# ScreenBoard.net
KiCad netlist of a schematic drawn in Altium Designer
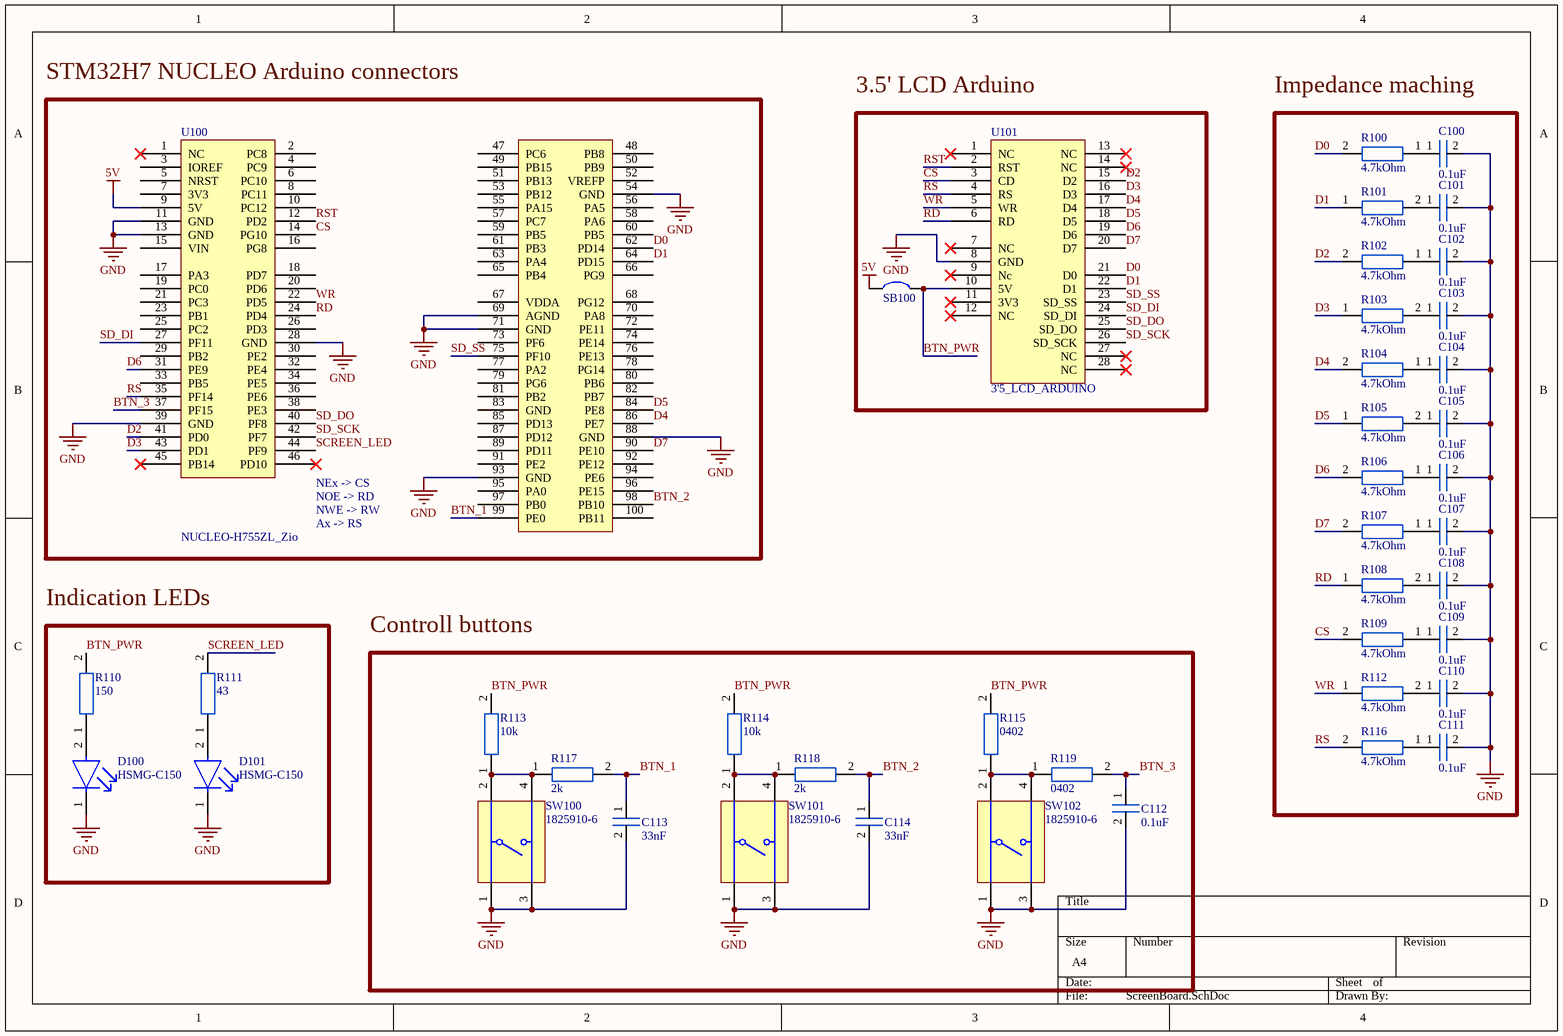
[diagram p0: ScreenBoard.SchDoc]

(export (version "E")
  (design (tool "Eeschema 10.0.6"))
  (components
    (comp (ref "C100")
      (value "0.1uF")
      (footprint "0402_footprint")
      (description "0402 capacitor")
      (libsource (lib "Schlib1") (part "Capacitor_0402"))
    )
    (comp (ref "C101")
      (value "0.1uF")
      (footprint "0402_footprint")
      (description "0402 capacitor")
      (libsource (lib "Schlib1") (part "Capacitor_0402"))
    )
    (comp (ref "C102")
      (value "0.1uF")
      (footprint "0402_footprint")
      (description "0402 capacitor")
      (libsource (lib "Schlib1") (part "Capacitor_0402"))
    )
    (comp (ref "C103")
      (value "0.1uF")
      (footprint "0402_footprint")
      (description "0402 capacitor")
      (libsource (lib "Schlib1") (part "Capacitor_0402"))
    )
    (comp (ref "C104")
      (value "0.1uF")
      (footprint "0402_footprint")
      (description "0402 capacitor")
      (libsource (lib "Schlib1") (part "Capacitor_0402"))
    )
    (comp (ref "C105")
      (value "0.1uF")
      (footprint "0402_footprint")
      (description "0402 capacitor")
      (libsource (lib "Schlib1") (part "Capacitor_0402"))
    )
    (comp (ref "C106")
      (value "0.1uF")
      (footprint "0402_footprint")
      (description "0402 capacitor")
      (libsource (lib "Schlib1") (part "Capacitor_0402"))
    )
    (comp (ref "C107")
      (value "0.1uF")
      (footprint "0402_footprint")
      (description "0402 capacitor")
      (libsource (lib "Schlib1") (part "Capacitor_0402"))
    )
    (comp (ref "C108")
      (value "0.1uF")
      (footprint "0402_footprint")
      (description "0402 capacitor")
      (libsource (lib "Schlib1") (part "Capacitor_0402"))
    )
    (comp (ref "C109")
      (value "0.1uF")
      (footprint "0402_footprint")
      (description "0402 capacitor")
      (libsource (lib "Schlib1") (part "Capacitor_0402"))
    )
    (comp (ref "C110")
      (value "0.1uF")
      (footprint "0402_footprint")
      (description "0402 capacitor")
      (libsource (lib "Schlib1") (part "Capacitor_0402"))
    )
    (comp (ref "C111")
      (value "0.1uF")
      (footprint "0402_footprint")
      (description "0402 capacitor")
      (libsource (lib "Schlib1") (part "Capacitor_0402"))
    )
    (comp (ref "C112")
      (value "0.1uF")
      (footprint "0402_footprint")
      (description "0402 capacitor")
      (libsource (lib "Schlib1") (part "Capacitor_0402"))
    )
    (comp (ref "C113")
      (value "33nF")
      (footprint "0402_footprint")
      (description "0402 capacitor")
      (libsource (lib "Schlib1") (part "Capacitor_0402"))
    )
    (comp (ref "C114")
      (value "33nF")
      (footprint "0402_footprint")
      (description "0402 capacitor")
      (libsource (lib "Schlib1") (part "Capacitor_0402"))
    )
    (comp (ref "D100")
      (value "HSMG-C150")
      (footprint "FP-HSMG-C150-MFG")
      (description "LED GREEN DIFFUSED 1206 SMD")
      (fields
        (field (name "MANUFACTURER") "Broadcom")
        (field (name "OCTOPART") "https://octopart.com/hsmg-c150-broadcom-71131304")
      )
      (libsource (lib "Altium Content Vault") (part "8706943c75ba83719d021d2fdc84c58"))
    )
    (comp (ref "D101")
      (value "HSMG-C150")
      (footprint "FP-HSMG-C150-MFG")
      (description "LED GREEN DIFFUSED 1206 SMD")
      (fields
        (field (name "MANUFACTURER") "Broadcom")
        (field (name "OCTOPART") "https://octopart.com/hsmg-c150-broadcom-71131304")
      )
      (libsource (lib "Altium Content Vault") (part "8706943c75ba83719d021d2fdc84c58"))
    )
    (comp (ref "R100")
      (value "4.7kOhm")
      (footprint "0402_footprint")
      (description "0402 resistor")
      (libsource (lib "Schlib1") (part "Resistor_0402"))
    )
    (comp (ref "R101")
      (value "4.7kOhm")
      (footprint "0402_footprint")
      (description "0402 resistor")
      (libsource (lib "Schlib1") (part "Resistor_0402"))
    )
    (comp (ref "R102")
      (value "4.7kOhm")
      (footprint "0402_footprint")
      (description "0402 resistor")
      (libsource (lib "Schlib1") (part "Resistor_0402"))
    )
    (comp (ref "R103")
      (value "4.7kOhm")
      (footprint "0402_footprint")
      (description "0402 resistor")
      (libsource (lib "Schlib1") (part "Resistor_0402"))
    )
    (comp (ref "R104")
      (value "4.7kOhm")
      (footprint "0402_footprint")
      (description "0402 resistor")
      (libsource (lib "Schlib1") (part "Resistor_0402"))
    )
    (comp (ref "R105")
      (value "4.7kOhm")
      (footprint "0402_footprint")
      (description "0402 resistor")
      (libsource (lib "Schlib1") (part "Resistor_0402"))
    )
    (comp (ref "R106")
      (value "4.7kOhm")
      (footprint "0402_footprint")
      (description "0402 resistor")
      (libsource (lib "Schlib1") (part "Resistor_0402"))
    )
    (comp (ref "R107")
      (value "4.7kOhm")
      (footprint "0402_footprint")
      (description "0402 resistor")
      (libsource (lib "Schlib1") (part "Resistor_0402"))
    )
    (comp (ref "R108")
      (value "4.7kOhm")
      (footprint "0402_footprint")
      (description "0402 resistor")
      (libsource (lib "Schlib1") (part "Resistor_0402"))
    )
    (comp (ref "R109")
      (value "4.7kOhm")
      (footprint "0402_footprint")
      (description "0402 resistor")
      (libsource (lib "Schlib1") (part "Resistor_0402"))
    )
    (comp (ref "R110")
      (value "150")
      (footprint "0402_footprint")
      (description "0402 resistor")
      (libsource (lib "Schlib1") (part "Resistor_0402"))
    )
    (comp (ref "R111")
      (value "43")
      (footprint "0402_footprint")
      (description "0402 resistor")
      (libsource (lib "Schlib1") (part "Resistor_0402"))
    )
    (comp (ref "R112")
      (value "4.7kOhm")
      (footprint "0402_footprint")
      (description "0402 resistor")
      (libsource (lib "Schlib1") (part "Resistor_0402"))
    )
    (comp (ref "R113")
      (value "10k")
      (footprint "0402_footprint")
      (description "0402 resistor")
      (libsource (lib "Schlib1") (part "Resistor_0402"))
    )
    (comp (ref "R114")
      (value "10k")
      (footprint "0402_footprint")
      (description "0402 resistor")
      (libsource (lib "Schlib1") (part "Resistor_0402"))
    )
    (comp (ref "R115")
      (value "0402")
      (footprint "0402_footprint")
      (description "0402 resistor")
      (libsource (lib "Schlib1") (part "Resistor_0402"))
    )
    (comp (ref "R116")
      (value "4.7kOhm")
      (footprint "0402_footprint")
      (description "0402 resistor")
      (libsource (lib "Schlib1") (part "Resistor_0402"))
    )
    (comp (ref "R117")
      (value "2k")
      (footprint "0402_footprint")
      (description "0402 resistor")
      (libsource (lib "Schlib1") (part "Resistor_0402"))
    )
    (comp (ref "R118")
      (value "2k")
      (footprint "0402_footprint")
      (description "0402 resistor")
      (libsource (lib "Schlib1") (part "Resistor_0402"))
    )
    (comp (ref "R119")
      (value "0402")
      (footprint "0402_footprint")
      (description "0402 resistor")
      (libsource (lib "Schlib1") (part "Resistor_0402"))
    )
    (comp (ref "SB100")
      (value "Solder_bridge")
      (footprint "SOLDER_BRIDGE")
      (libsource (lib "Schlib1") (part "Solder_bridge"))
    )
    (comp (ref "SW100")
      (value "1825910-6")
      (footprint "TECO-1825910-6_V")
      (description "Tact Switch, SPST-NO, 0.05 A, -35 to 85 degC, 4-Pin THD, RoHS, Bulk")
      (fields (field (name "MANUFACTURER") "TE Connectivity"))
      (libsource (lib "Altium Content Vault") (part "SW-SPST-4_A"))
    )
    (comp (ref "SW101")
      (value "1825910-6")
      (footprint "TECO-1825910-6_V")
      (description "Tact Switch, SPST-NO, 0.05 A, -35 to 85 degC, 4-Pin THD, RoHS, Bulk")
      (fields (field (name "MANUFACTURER") "TE Connectivity"))
      (libsource (lib "Altium Content Vault") (part "SW-SPST-4_A"))
    )
    (comp (ref "SW102")
      (value "1825910-6")
      (footprint "TECO-1825910-6_V")
      (description "Tact Switch, SPST-NO, 0.05 A, -35 to 85 degC, 4-Pin THD, RoHS, Bulk")
      (fields (field (name "MANUFACTURER") "TE Connectivity"))
      (libsource (lib "Altium Content Vault") (part "SW-SPST-4_A"))
    )
    (comp (ref "U100")
      (value "NUCLEO-H755ZL_Zio")
      (footprint "H7/H5_NUCLEO_Zio")
      (libsource (lib "Schlib1") (part "NUCLEO-H755ZL_Zio"))
    )
    (comp (ref "U101")
      (value "3'5_LCD_ARDUINO")
      (footprint "3'5_LCD_ARDUINO")
      (libsource (lib "Schlib1") (part "3'5_LCD_ARDUINO"))
    )
  )
  (nets
    (net (code "1") (name "/BTN_1") (class "Default")
      (node (ref "C113") (pin "1") (pinfunction "1_1") (pintype "passive"))
      (node (ref "R117") (pin "2") (pinfunction "2_2") (pintype "passive"))
      (node (ref "U100") (pin "99") (pinfunction "PE0_99") (pintype "passive"))
    )
    (net (code "2") (name "/BTN_2") (class "Default")
      (node (ref "C114") (pin "1") (pinfunction "1_1") (pintype "passive"))
      (node (ref "R118") (pin "2") (pinfunction "2_2") (pintype "passive"))
      (node (ref "U100") (pin "98") (pinfunction "PB10_98") (pintype "passive"))
    )
    (net (code "3") (name "/BTN_3") (class "Default")
      (node (ref "C112") (pin "1") (pinfunction "1_1") (pintype "passive"))
      (node (ref "R119") (pin "2") (pinfunction "2_2") (pintype "passive"))
      (node (ref "U100") (pin "37") (pinfunction "PF15_37") (pintype "passive"))
    )
    (net (code "4") (name "/BTN_PWR") (class "Default")
      (node (ref "R110") (pin "2") (pinfunction "2_2") (pintype "passive"))
      (node (ref "R113") (pin "2") (pinfunction "2_2") (pintype "passive"))
      (node (ref "R114") (pin "2") (pinfunction "2_2") (pintype "passive"))
      (node (ref "R115") (pin "2") (pinfunction "2_2") (pintype "passive"))
      (node (ref "SB100") (pin "2") (pinfunction "2_2") (pintype "passive"))
      (node (ref "U101") (pin "10") (pinfunction "5V_10") (pintype "passive"))
    )
    (net (code "5") (name "/CS") (class "Default")
      (node (ref "R109") (pin "2") (pinfunction "2_2") (pintype "passive"))
      (node (ref "U100") (pin "14") (pinfunction "PG10_14") (pintype "passive"))
      (node (ref "U101") (pin "3") (pinfunction "CD_3") (pintype "passive"))
    )
    (net (code "6") (name "/D0") (class "Default")
      (node (ref "R100") (pin "2") (pinfunction "2_2") (pintype "passive"))
      (node (ref "U100") (pin "62") (pinfunction "PD14_62") (pintype "passive"))
      (node (ref "U101") (pin "21") (pinfunction "D0_21") (pintype "passive"))
    )
    (net (code "7") (name "/D1") (class "Default")
      (node (ref "R101") (pin "1") (pinfunction "1_1") (pintype "passive"))
      (node (ref "U100") (pin "64") (pinfunction "PD15_64") (pintype "passive"))
      (node (ref "U101") (pin "22") (pinfunction "D1_22") (pintype "passive"))
    )
    (net (code "8") (name "/D2") (class "Default")
      (node (ref "R102") (pin "2") (pinfunction "2_2") (pintype "passive"))
      (node (ref "U100") (pin "41") (pinfunction "PD0_41") (pintype "passive"))
      (node (ref "U101") (pin "15") (pinfunction "D2_15") (pintype "passive"))
    )
    (net (code "9") (name "/D3") (class "Default")
      (node (ref "R103") (pin "1") (pinfunction "1_1") (pintype "passive"))
      (node (ref "U100") (pin "43") (pinfunction "PD1_43") (pintype "passive"))
      (node (ref "U101") (pin "16") (pinfunction "D3_16") (pintype "passive"))
    )
    (net (code "10") (name "/D4") (class "Default")
      (node (ref "R104") (pin "2") (pinfunction "2_2") (pintype "passive"))
      (node (ref "U100") (pin "86") (pinfunction "PE7_86") (pintype "passive"))
      (node (ref "U101") (pin "17") (pinfunction "D4_17") (pintype "passive"))
    )
    (net (code "11") (name "/D5") (class "Default")
      (node (ref "R105") (pin "1") (pinfunction "1_1") (pintype "passive"))
      (node (ref "U100") (pin "84") (pinfunction "PE8_84") (pintype "passive"))
      (node (ref "U101") (pin "18") (pinfunction "D5_18") (pintype "passive"))
    )
    (net (code "12") (name "/D6") (class "Default")
      (node (ref "R106") (pin "2") (pinfunction "2_2") (pintype "passive"))
      (node (ref "U100") (pin "31") (pinfunction "PE9_31") (pintype "passive"))
      (node (ref "U101") (pin "19") (pinfunction "D6_19") (pintype "passive"))
    )
    (net (code "13") (name "/D7") (class "Default")
      (node (ref "R107") (pin "2") (pinfunction "2_2") (pintype "passive"))
      (node (ref "U100") (pin "90") (pinfunction "PE10_90") (pintype "passive"))
      (node (ref "U101") (pin "20") (pinfunction "D7_20") (pintype "passive"))
    )
    (net (code "14") (name "/RD") (class "Default")
      (node (ref "R108") (pin "1") (pinfunction "1_1") (pintype "passive"))
      (node (ref "U100") (pin "24") (pinfunction "PD4_24") (pintype "passive"))
      (node (ref "U101") (pin "6") (pinfunction "RD_6") (pintype "passive"))
    )
    (net (code "15") (name "/RS") (class "Default")
      (node (ref "R116") (pin "2") (pinfunction "2_2") (pintype "passive"))
      (node (ref "U100") (pin "35") (pinfunction "PF14_35") (pintype "passive"))
      (node (ref "U101") (pin "4") (pinfunction "RS_4") (pintype "passive"))
    )
    (net (code "16") (name "/RST") (class "Default")
      (node (ref "U100") (pin "12") (pinfunction "PD2_12") (pintype "passive"))
      (node (ref "U101") (pin "2") (pinfunction "RST_2") (pintype "passive"))
    )
    (net (code "17") (name "/SCREEN_LED") (class "Default")
      (node (ref "R111") (pin "2") (pinfunction "2_2") (pintype "passive"))
      (node (ref "U100") (pin "44") (pinfunction "PF9_44") (pintype "passive"))
    )
    (net (code "18") (name "/SD_DI") (class "Default")
      (node (ref "U100") (pin "27") (pinfunction "PF11_27") (pintype "passive"))
      (node (ref "U101") (pin "24") (pinfunction "SD_DI_24") (pintype "passive"))
    )
    (net (code "19") (name "/SD_DO") (class "Default")
      (node (ref "U100") (pin "40") (pinfunction "PF8_40") (pintype "passive"))
      (node (ref "U101") (pin "25") (pinfunction "SD_DO_25") (pintype "passive"))
    )
    (net (code "20") (name "/SD_SCK") (class "Default")
      (node (ref "U100") (pin "42") (pinfunction "PF7_42") (pintype "passive"))
      (node (ref "U101") (pin "26") (pinfunction "SD_SCK_26") (pintype "passive"))
    )
    (net (code "21") (name "/SD_SS") (class "Default")
      (node (ref "U100") (pin "75") (pinfunction "PF10_75") (pintype "passive"))
      (node (ref "U101") (pin "23") (pinfunction "SD_SS_23") (pintype "passive"))
    )
    (net (code "22") (name "/WR") (class "Default")
      (node (ref "R112") (pin "1") (pinfunction "1_1") (pintype "passive"))
      (node (ref "U100") (pin "22") (pinfunction "PD5_22") (pintype "passive"))
      (node (ref "U101") (pin "5") (pinfunction "WR_5") (pintype "passive"))
    )
    (net (code "23") (name "5V") (class "Default")
      (node (ref "SB100") (pin "1") (pinfunction "1_1") (pintype "passive"))
      (node (ref "U100") (pin "9") (pinfunction "5V_9") (pintype "passive"))
    )
    (net (code "24") (name "GND") (class "Default")
      (node (ref "C100") (pin "2") (pinfunction "2_2") (pintype "passive"))
      (node (ref "C101") (pin "2") (pinfunction "2_2") (pintype "passive"))
      (node (ref "C102") (pin "2") (pinfunction "2_2") (pintype "passive"))
      (node (ref "C103") (pin "2") (pinfunction "2_2") (pintype "passive"))
      (node (ref "C104") (pin "2") (pinfunction "2_2") (pintype "passive"))
      (node (ref "C105") (pin "2") (pinfunction "2_2") (pintype "passive"))
      (node (ref "C106") (pin "2") (pinfunction "2_2") (pintype "passive"))
      (node (ref "C107") (pin "2") (pinfunction "2_2") (pintype "passive"))
      (node (ref "C108") (pin "2") (pinfunction "2_2") (pintype "passive"))
      (node (ref "C109") (pin "2") (pinfunction "2_2") (pintype "passive"))
      (node (ref "C110") (pin "2") (pinfunction "2_2") (pintype "passive"))
      (node (ref "C111") (pin "2") (pinfunction "2_2") (pintype "passive"))
      (node (ref "C112") (pin "2") (pinfunction "2_2") (pintype "passive"))
      (node (ref "C113") (pin "2") (pinfunction "2_2") (pintype "passive"))
      (node (ref "C114") (pin "2") (pinfunction "2_2") (pintype "passive"))
      (node (ref "D100") (pin "1") (pinfunction "C_1") (pintype "passive"))
      (node (ref "D101") (pin "1") (pinfunction "C_1") (pintype "passive"))
      (node (ref "SW100") (pin "1") (pinfunction "1_1") (pintype "passive"))
      (node (ref "SW100") (pin "3") (pinfunction "3_3") (pintype "passive"))
      (node (ref "SW101") (pin "1") (pinfunction "1_1") (pintype "passive"))
      (node (ref "SW101") (pin "3") (pinfunction "3_3") (pintype "passive"))
      (node (ref "SW102") (pin "1") (pinfunction "1_1") (pintype "passive"))
      (node (ref "SW102") (pin "3") (pinfunction "3_3") (pintype "passive"))
      (node (ref "U100") (pin "11") (pinfunction "GND_11") (pintype "passive"))
      (node (ref "U100") (pin "13") (pinfunction "GND_13") (pintype "passive"))
      (node (ref "U100") (pin "28") (pinfunction "GND_28") (pintype "passive"))
      (node (ref "U100") (pin "39") (pinfunction "GND_39") (pintype "passive"))
      (node (ref "U100") (pin "54") (pinfunction "GND_54") (pintype "passive"))
      (node (ref "U100") (pin "69") (pinfunction "AGND_69") (pintype "passive"))
      (node (ref "U100") (pin "71") (pinfunction "GND_71") (pintype "passive"))
      (node (ref "U100") (pin "88") (pinfunction "GND_88") (pintype "passive"))
      (node (ref "U100") (pin "93") (pinfunction "GND_93") (pintype "passive"))
      (node (ref "U101") (pin "8") (pinfunction "GND_8") (pintype "passive"))
    )
    (net (code "25") (name "Net-(C100-Pad1)") (class "Default")
      (node (ref "C100") (pin "1") (pinfunction "1_1") (pintype "passive"))
      (node (ref "R100") (pin "1") (pinfunction "1_1") (pintype "passive"))
    )
    (net (code "26") (name "Net-(C101-Pad1)") (class "Default")
      (node (ref "C101") (pin "1") (pinfunction "1_1") (pintype "passive"))
      (node (ref "R101") (pin "2") (pinfunction "2_2") (pintype "passive"))
    )
    (net (code "27") (name "Net-(C102-Pad1)") (class "Default")
      (node (ref "C102") (pin "1") (pinfunction "1_1") (pintype "passive"))
      (node (ref "R102") (pin "1") (pinfunction "1_1") (pintype "passive"))
    )
    (net (code "28") (name "Net-(C103-Pad1)") (class "Default")
      (node (ref "C103") (pin "1") (pinfunction "1_1") (pintype "passive"))
      (node (ref "R103") (pin "2") (pinfunction "2_2") (pintype "passive"))
    )
    (net (code "29") (name "Net-(C104-Pad1)") (class "Default")
      (node (ref "C104") (pin "1") (pinfunction "1_1") (pintype "passive"))
      (node (ref "R104") (pin "1") (pinfunction "1_1") (pintype "passive"))
    )
    (net (code "30") (name "Net-(C105-Pad1)") (class "Default")
      (node (ref "C105") (pin "1") (pinfunction "1_1") (pintype "passive"))
      (node (ref "R105") (pin "2") (pinfunction "2_2") (pintype "passive"))
    )
    (net (code "31") (name "Net-(C106-Pad1)") (class "Default")
      (node (ref "C106") (pin "1") (pinfunction "1_1") (pintype "passive"))
      (node (ref "R106") (pin "1") (pinfunction "1_1") (pintype "passive"))
    )
    (net (code "32") (name "Net-(C107-Pad1)") (class "Default")
      (node (ref "C107") (pin "1") (pinfunction "1_1") (pintype "passive"))
      (node (ref "R107") (pin "1") (pinfunction "1_1") (pintype "passive"))
    )
    (net (code "33") (name "Net-(C108-Pad1)") (class "Default")
      (node (ref "C108") (pin "1") (pinfunction "1_1") (pintype "passive"))
      (node (ref "R108") (pin "2") (pinfunction "2_2") (pintype "passive"))
    )
    (net (code "34") (name "Net-(C109-Pad1)") (class "Default")
      (node (ref "C109") (pin "1") (pinfunction "1_1") (pintype "passive"))
      (node (ref "R109") (pin "1") (pinfunction "1_1") (pintype "passive"))
    )
    (net (code "35") (name "Net-(C110-Pad1)") (class "Default")
      (node (ref "C110") (pin "1") (pinfunction "1_1") (pintype "passive"))
      (node (ref "R112") (pin "2") (pinfunction "2_2") (pintype "passive"))
    )
    (net (code "36") (name "Net-(C111-Pad1)") (class "Default")
      (node (ref "C111") (pin "1") (pinfunction "1_1") (pintype "passive"))
      (node (ref "R116") (pin "1") (pinfunction "1_1") (pintype "passive"))
    )
    (net (code "37") (name "Net-(D100-A)") (class "Default")
      (node (ref "D100") (pin "2") (pinfunction "A_2") (pintype "passive"))
      (node (ref "R110") (pin "1") (pinfunction "1_1") (pintype "passive"))
    )
    (net (code "38") (name "Net-(D101-A)") (class "Default")
      (node (ref "D101") (pin "2") (pinfunction "A_2") (pintype "passive"))
      (node (ref "R111") (pin "1") (pinfunction "1_1") (pintype "passive"))
    )
    (net (code "39") (name "Net-(R113-Pad1)") (class "Default")
      (node (ref "R113") (pin "1") (pinfunction "1_1") (pintype "passive"))
      (node (ref "R117") (pin "1") (pinfunction "1_1") (pintype "passive"))
      (node (ref "SW100") (pin "2") (pinfunction "2_2") (pintype "passive"))
      (node (ref "SW100") (pin "4") (pinfunction "4_4") (pintype "passive"))
    )
    (net (code "40") (name "Net-(R114-Pad1)") (class "Default")
      (node (ref "R114") (pin "1") (pinfunction "1_1") (pintype "passive"))
      (node (ref "R118") (pin "1") (pinfunction "1_1") (pintype "passive"))
      (node (ref "SW101") (pin "2") (pinfunction "2_2") (pintype "passive"))
      (node (ref "SW101") (pin "4") (pinfunction "4_4") (pintype "passive"))
    )
    (net (code "41") (name "Net-(R115-Pad1)") (class "Default")
      (node (ref "R115") (pin "1") (pinfunction "1_1") (pintype "passive"))
      (node (ref "R119") (pin "1") (pinfunction "1_1") (pintype "passive"))
      (node (ref "SW102") (pin "2") (pinfunction "2_2") (pintype "passive"))
      (node (ref "SW102") (pin "4") (pinfunction "4_4") (pintype "passive"))
    )
    (net (code "42") (name "unconnected-(U100-3V3-Pad7)") (class "Default")
      (node (ref "U100") (pin "7") (pinfunction "3V3_7") (pintype "passive"))
    )
    (net (code "43") (name "unconnected-(U100-GND-Pad83)") (class "Default")
      (node (ref "U100") (pin "83") (pinfunction "GND_83") (pintype "passive"))
    )
    (net (code "44") (name "unconnected-(U100-IOREF-Pad3)") (class "Default")
      (node (ref "U100") (pin "3") (pinfunction "IOREF_3") (pintype "passive"))
    )
    (net (code "45") (name "unconnected-(U100-NC-Pad1)") (class "Default")
      (node (ref "U100") (pin "1") (pinfunction "NC_1") (pintype "passive+no_connect"))
    )
    (net (code "46") (name "unconnected-(U100-NRST-Pad5)") (class "Default")
      (node (ref "U100") (pin "5") (pinfunction "NRST_5") (pintype "passive"))
    )
    (net (code "47") (name "unconnected-(U100-PA0-Pad95)") (class "Default")
      (node (ref "U100") (pin "95") (pinfunction "PA0_95") (pintype "passive"))
    )
    (net (code "48") (name "unconnected-(U100-PA2-Pad77)") (class "Default")
      (node (ref "U100") (pin "77") (pinfunction "PA2_77") (pintype "passive"))
    )
    (net (code "49") (name "unconnected-(U100-PA3-Pad17)") (class "Default")
      (node (ref "U100") (pin "17") (pinfunction "PA3_17") (pintype "passive"))
    )
    (net (code "50") (name "unconnected-(U100-PA4-Pad63)") (class "Default")
      (node (ref "U100") (pin "63") (pinfunction "PA4_63") (pintype "passive"))
    )
    (net (code "51") (name "unconnected-(U100-PA5-Pad56)") (class "Default")
      (node (ref "U100") (pin "56") (pinfunction "PA5_56") (pintype "passive"))
    )
    (net (code "52") (name "unconnected-(U100-PA6-Pad58)") (class "Default")
      (node (ref "U100") (pin "58") (pinfunction "PA6_58") (pintype "passive"))
    )
    (net (code "53") (name "unconnected-(U100-PA8-Pad70)") (class "Default")
      (node (ref "U100") (pin "70") (pinfunction "PA8_70") (pintype "passive"))
    )
    (net (code "54") (name "unconnected-(U100-PA15-Pad55)") (class "Default")
      (node (ref "U100") (pin "55") (pinfunction "PA15_55") (pintype "passive"))
    )
    (net (code "55") (name "unconnected-(U100-PB0-Pad97)") (class "Default")
      (node (ref "U100") (pin "97") (pinfunction "PB0_97") (pintype "passive"))
    )
    (net (code "56") (name "unconnected-(U100-PB1-Pad23)") (class "Default")
      (node (ref "U100") (pin "23") (pinfunction "PB1_23") (pintype "passive"))
    )
    (net (code "57") (name "unconnected-(U100-PB2-Pad29)") (class "Default")
      (node (ref "U100") (pin "29") (pinfunction "PB2_29") (pintype "passive"))
    )
    (net (code "58") (name "unconnected-(U100-PB2-Pad81)") (class "Default")
      (node (ref "U100") (pin "81") (pinfunction "PB2_81") (pintype "passive"))
    )
    (net (code "59") (name "unconnected-(U100-PB3-Pad61)") (class "Default")
      (node (ref "U100") (pin "61") (pinfunction "PB3_61") (pintype "passive"))
    )
    (net (code "60") (name "unconnected-(U100-PB4-Pad65)") (class "Default")
      (node (ref "U100") (pin "65") (pinfunction "PB4_65") (pintype "passive"))
    )
    (net (code "61") (name "unconnected-(U100-PB5-Pad33)") (class "Default")
      (node (ref "U100") (pin "33") (pinfunction "PB5_33") (pintype "passive"))
    )
    (net (code "62") (name "unconnected-(U100-PB5-Pad59)") (class "Default")
      (node (ref "U100") (pin "59") (pinfunction "PB5_59") (pintype "passive"))
    )
    (net (code "63") (name "unconnected-(U100-PB5-Pad60)") (class "Default")
      (node (ref "U100") (pin "60") (pinfunction "PB5_60") (pintype "passive"))
    )
    (net (code "64") (name "unconnected-(U100-PB6-Pad80)") (class "Default")
      (node (ref "U100") (pin "80") (pinfunction "PB6_80") (pintype "passive"))
    )
    (net (code "65") (name "unconnected-(U100-PB7-Pad82)") (class "Default")
      (node (ref "U100") (pin "82") (pinfunction "PB7_82") (pintype "passive"))
    )
    (net (code "66") (name "unconnected-(U100-PB8-Pad48)") (class "Default")
      (node (ref "U100") (pin "48") (pinfunction "PB8_48") (pintype "passive"))
    )
    (net (code "67") (name "unconnected-(U100-PB9-Pad50)") (class "Default")
      (node (ref "U100") (pin "50") (pinfunction "PB9_50") (pintype "passive"))
    )
    (net (code "68") (name "unconnected-(U100-PB11-Pad100)") (class "Default")
      (node (ref "U100") (pin "100") (pinfunction "PB11_100") (pintype "passive"))
    )
    (net (code "69") (name "unconnected-(U100-PB12-Pad53)") (class "Default")
      (node (ref "U100") (pin "53") (pinfunction "PB12_53") (pintype "passive"))
    )
    (net (code "70") (name "unconnected-(U100-PB13-Pad51)") (class "Default")
      (node (ref "U100") (pin "51") (pinfunction "PB13_51") (pintype "passive"))
    )
    (net (code "71") (name "unconnected-(U100-PB14-Pad45)") (class "Default")
      (node (ref "U100") (pin "45") (pinfunction "PB14_45") (pintype "passive+no_connect"))
    )
    (net (code "72") (name "unconnected-(U100-PB15-Pad49)") (class "Default")
      (node (ref "U100") (pin "49") (pinfunction "PB15_49") (pintype "passive"))
    )
    (net (code "73") (name "unconnected-(U100-PC0-Pad19)") (class "Default")
      (node (ref "U100") (pin "19") (pinfunction "PC0_19") (pintype "passive"))
    )
    (net (code "74") (name "unconnected-(U100-PC2-Pad25)") (class "Default")
      (node (ref "U100") (pin "25") (pinfunction "PC2_25") (pintype "passive"))
    )
    (net (code "75") (name "unconnected-(U100-PC3-Pad21)") (class "Default")
      (node (ref "U100") (pin "21") (pinfunction "PC3_21") (pintype "passive"))
    )
    (net (code "76") (name "unconnected-(U100-PC6-Pad47)") (class "Default")
      (node (ref "U100") (pin "47") (pinfunction "PC6_47") (pintype "passive"))
    )
    (net (code "77") (name "unconnected-(U100-PC7-Pad57)") (class "Default")
      (node (ref "U100") (pin "57") (pinfunction "PC7_57") (pintype "passive"))
    )
    (net (code "78") (name "unconnected-(U100-PC8-Pad2)") (class "Default")
      (node (ref "U100") (pin "2") (pinfunction "PC8_2") (pintype "passive"))
    )
    (net (code "79") (name "unconnected-(U100-PC9-Pad4)") (class "Default")
      (node (ref "U100") (pin "4") (pinfunction "PC9_4") (pintype "passive"))
    )
    (net (code "80") (name "unconnected-(U100-PC10-Pad6)") (class "Default")
      (node (ref "U100") (pin "6") (pinfunction "PC10_6") (pintype "passive"))
    )
    (net (code "81") (name "unconnected-(U100-PC11-Pad8)") (class "Default")
      (node (ref "U100") (pin "8") (pinfunction "PC11_8") (pintype "passive"))
    )
    (net (code "82") (name "unconnected-(U100-PC12-Pad10)") (class "Default")
      (node (ref "U100") (pin "10") (pinfunction "PC12_10") (pintype "passive"))
    )
    (net (code "83") (name "unconnected-(U100-PD3-Pad26)") (class "Default")
      (node (ref "U100") (pin "26") (pinfunction "PD3_26") (pintype "passive"))
    )
    (net (code "84") (name "unconnected-(U100-PD6-Pad20)") (class "Default")
      (node (ref "U100") (pin "20") (pinfunction "PD6_20") (pintype "passive"))
    )
    (net (code "85") (name "unconnected-(U100-PD7-Pad18)") (class "Default")
      (node (ref "U100") (pin "18") (pinfunction "PD7_18") (pintype "passive"))
    )
    (net (code "86") (name "unconnected-(U100-PD10-Pad46)") (class "Default")
      (node (ref "U100") (pin "46") (pinfunction "PD10_46") (pintype "passive+no_connect"))
    )
    (net (code "87") (name "unconnected-(U100-PD11-Pad89)") (class "Default")
      (node (ref "U100") (pin "89") (pinfunction "PD11_89") (pintype "passive"))
    )
    (net (code "88") (name "unconnected-(U100-PD12-Pad87)") (class "Default")
      (node (ref "U100") (pin "87") (pinfunction "PD12_87") (pintype "passive"))
    )
    (net (code "89") (name "unconnected-(U100-PD13-Pad85)") (class "Default")
      (node (ref "U100") (pin "85") (pinfunction "PD13_85") (pintype "passive"))
    )
    (net (code "90") (name "unconnected-(U100-PE2-Pad30)") (class "Default")
      (node (ref "U100") (pin "30") (pinfunction "PE2_30") (pintype "passive"))
    )
    (net (code "91") (name "unconnected-(U100-PE2-Pad91)") (class "Default")
      (node (ref "U100") (pin "91") (pinfunction "PE2_91") (pintype "passive"))
    )
    (net (code "92") (name "unconnected-(U100-PE3-Pad38)") (class "Default")
      (node (ref "U100") (pin "38") (pinfunction "PE3_38") (pintype "passive"))
    )
    (net (code "93") (name "unconnected-(U100-PE4-Pad32)") (class "Default")
      (node (ref "U100") (pin "32") (pinfunction "PE4_32") (pintype "passive"))
    )
    (net (code "94") (name "unconnected-(U100-PE5-Pad34)") (class "Default")
      (node (ref "U100") (pin "34") (pinfunction "PE5_34") (pintype "passive"))
    )
    (net (code "95") (name "unconnected-(U100-PE6-Pad36)") (class "Default")
      (node (ref "U100") (pin "36") (pinfunction "PE6_36") (pintype "passive"))
    )
    (net (code "96") (name "unconnected-(U100-PE6-Pad94)") (class "Default")
      (node (ref "U100") (pin "94") (pinfunction "PE6_94") (pintype "passive"))
    )
    (net (code "97") (name "unconnected-(U100-PE11-Pad72)") (class "Default")
      (node (ref "U100") (pin "72") (pinfunction "PE11_72") (pintype "passive"))
    )
    (net (code "98") (name "unconnected-(U100-PE12-Pad92)") (class "Default")
      (node (ref "U100") (pin "92") (pinfunction "PE12_92") (pintype "passive"))
    )
    (net (code "99") (name "unconnected-(U100-PE13-Pad76)") (class "Default")
      (node (ref "U100") (pin "76") (pinfunction "PE13_76") (pintype "passive"))
    )
    (net (code "100") (name "unconnected-(U100-PE14-Pad74)") (class "Default")
      (node (ref "U100") (pin "74") (pinfunction "PE14_74") (pintype "passive"))
    )
    (net (code "101") (name "unconnected-(U100-PE15-Pad96)") (class "Default")
      (node (ref "U100") (pin "96") (pinfunction "PE15_96") (pintype "passive"))
    )
    (net (code "102") (name "unconnected-(U100-PF6-Pad73)") (class "Default")
      (node (ref "U100") (pin "73") (pinfunction "PF6_73") (pintype "passive"))
    )
    (net (code "103") (name "unconnected-(U100-PG6-Pad79)") (class "Default")
      (node (ref "U100") (pin "79") (pinfunction "PG6_79") (pintype "passive"))
    )
    (net (code "104") (name "unconnected-(U100-PG8-Pad16)") (class "Default")
      (node (ref "U100") (pin "16") (pinfunction "PG8_16") (pintype "passive"))
    )
    (net (code "105") (name "unconnected-(U100-PG9-Pad66)") (class "Default")
      (node (ref "U100") (pin "66") (pinfunction "PG9_66") (pintype "passive"))
    )
    (net (code "106") (name "unconnected-(U100-PG12-Pad68)") (class "Default")
      (node (ref "U100") (pin "68") (pinfunction "PG12_68") (pintype "passive"))
    )
    (net (code "107") (name "unconnected-(U100-PG14-Pad78)") (class "Default")
      (node (ref "U100") (pin "78") (pinfunction "PG14_78") (pintype "passive"))
    )
    (net (code "108") (name "unconnected-(U100-VDDA-Pad67)") (class "Default")
      (node (ref "U100") (pin "67") (pinfunction "VDDA_67") (pintype "passive"))
    )
    (net (code "109") (name "unconnected-(U100-VIN-Pad15)") (class "Default")
      (node (ref "U100") (pin "15") (pinfunction "VIN_15") (pintype "passive"))
    )
    (net (code "110") (name "unconnected-(U100-VREFP-Pad52)") (class "Default")
      (node (ref "U100") (pin "52") (pinfunction "VREFP_52") (pintype "passive"))
    )
    (net (code "111") (name "unconnected-(U101-3V3-Pad11)") (class "Default")
      (node (ref "U101") (pin "11") (pinfunction "3V3_11") (pintype "passive+no_connect"))
    )
    (net (code "112") (name "unconnected-(U101-NC-Pad1)") (class "Default")
      (node (ref "U101") (pin "1") (pinfunction "NC_1") (pintype "passive+no_connect"))
    )
    (net (code "113") (name "unconnected-(U101-NC-Pad7)") (class "Default")
      (node (ref "U101") (pin "7") (pinfunction "NC_7") (pintype "passive+no_connect"))
    )
    (net (code "114") (name "unconnected-(U101-NC-Pad12)") (class "Default")
      (node (ref "U101") (pin "12") (pinfunction "NC_12") (pintype "passive+no_connect"))
    )
    (net (code "115") (name "unconnected-(U101-NC-Pad13)") (class "Default")
      (node (ref "U101") (pin "13") (pinfunction "NC_13") (pintype "passive+no_connect"))
    )
    (net (code "116") (name "unconnected-(U101-NC-Pad14)") (class "Default")
      (node (ref "U101") (pin "14") (pinfunction "NC_14") (pintype "passive+no_connect"))
    )
    (net (code "117") (name "unconnected-(U101-NC-Pad27)") (class "Default")
      (node (ref "U101") (pin "27") (pinfunction "NC_27") (pintype "passive+no_connect"))
    )
    (net (code "118") (name "unconnected-(U101-NC-Pad28)") (class "Default")
      (node (ref "U101") (pin "28") (pinfunction "NC_28") (pintype "passive+no_connect"))
    )
    (net (code "119") (name "unconnected-(U101-Nc-Pad9)") (class "Default")
      (node (ref "U101") (pin "9") (pinfunction "Nc_9") (pintype "passive+no_connect"))
    )
  )
)
